# octopus_sch.net
KiCad netlist of a schematic drawn in Altium Designer
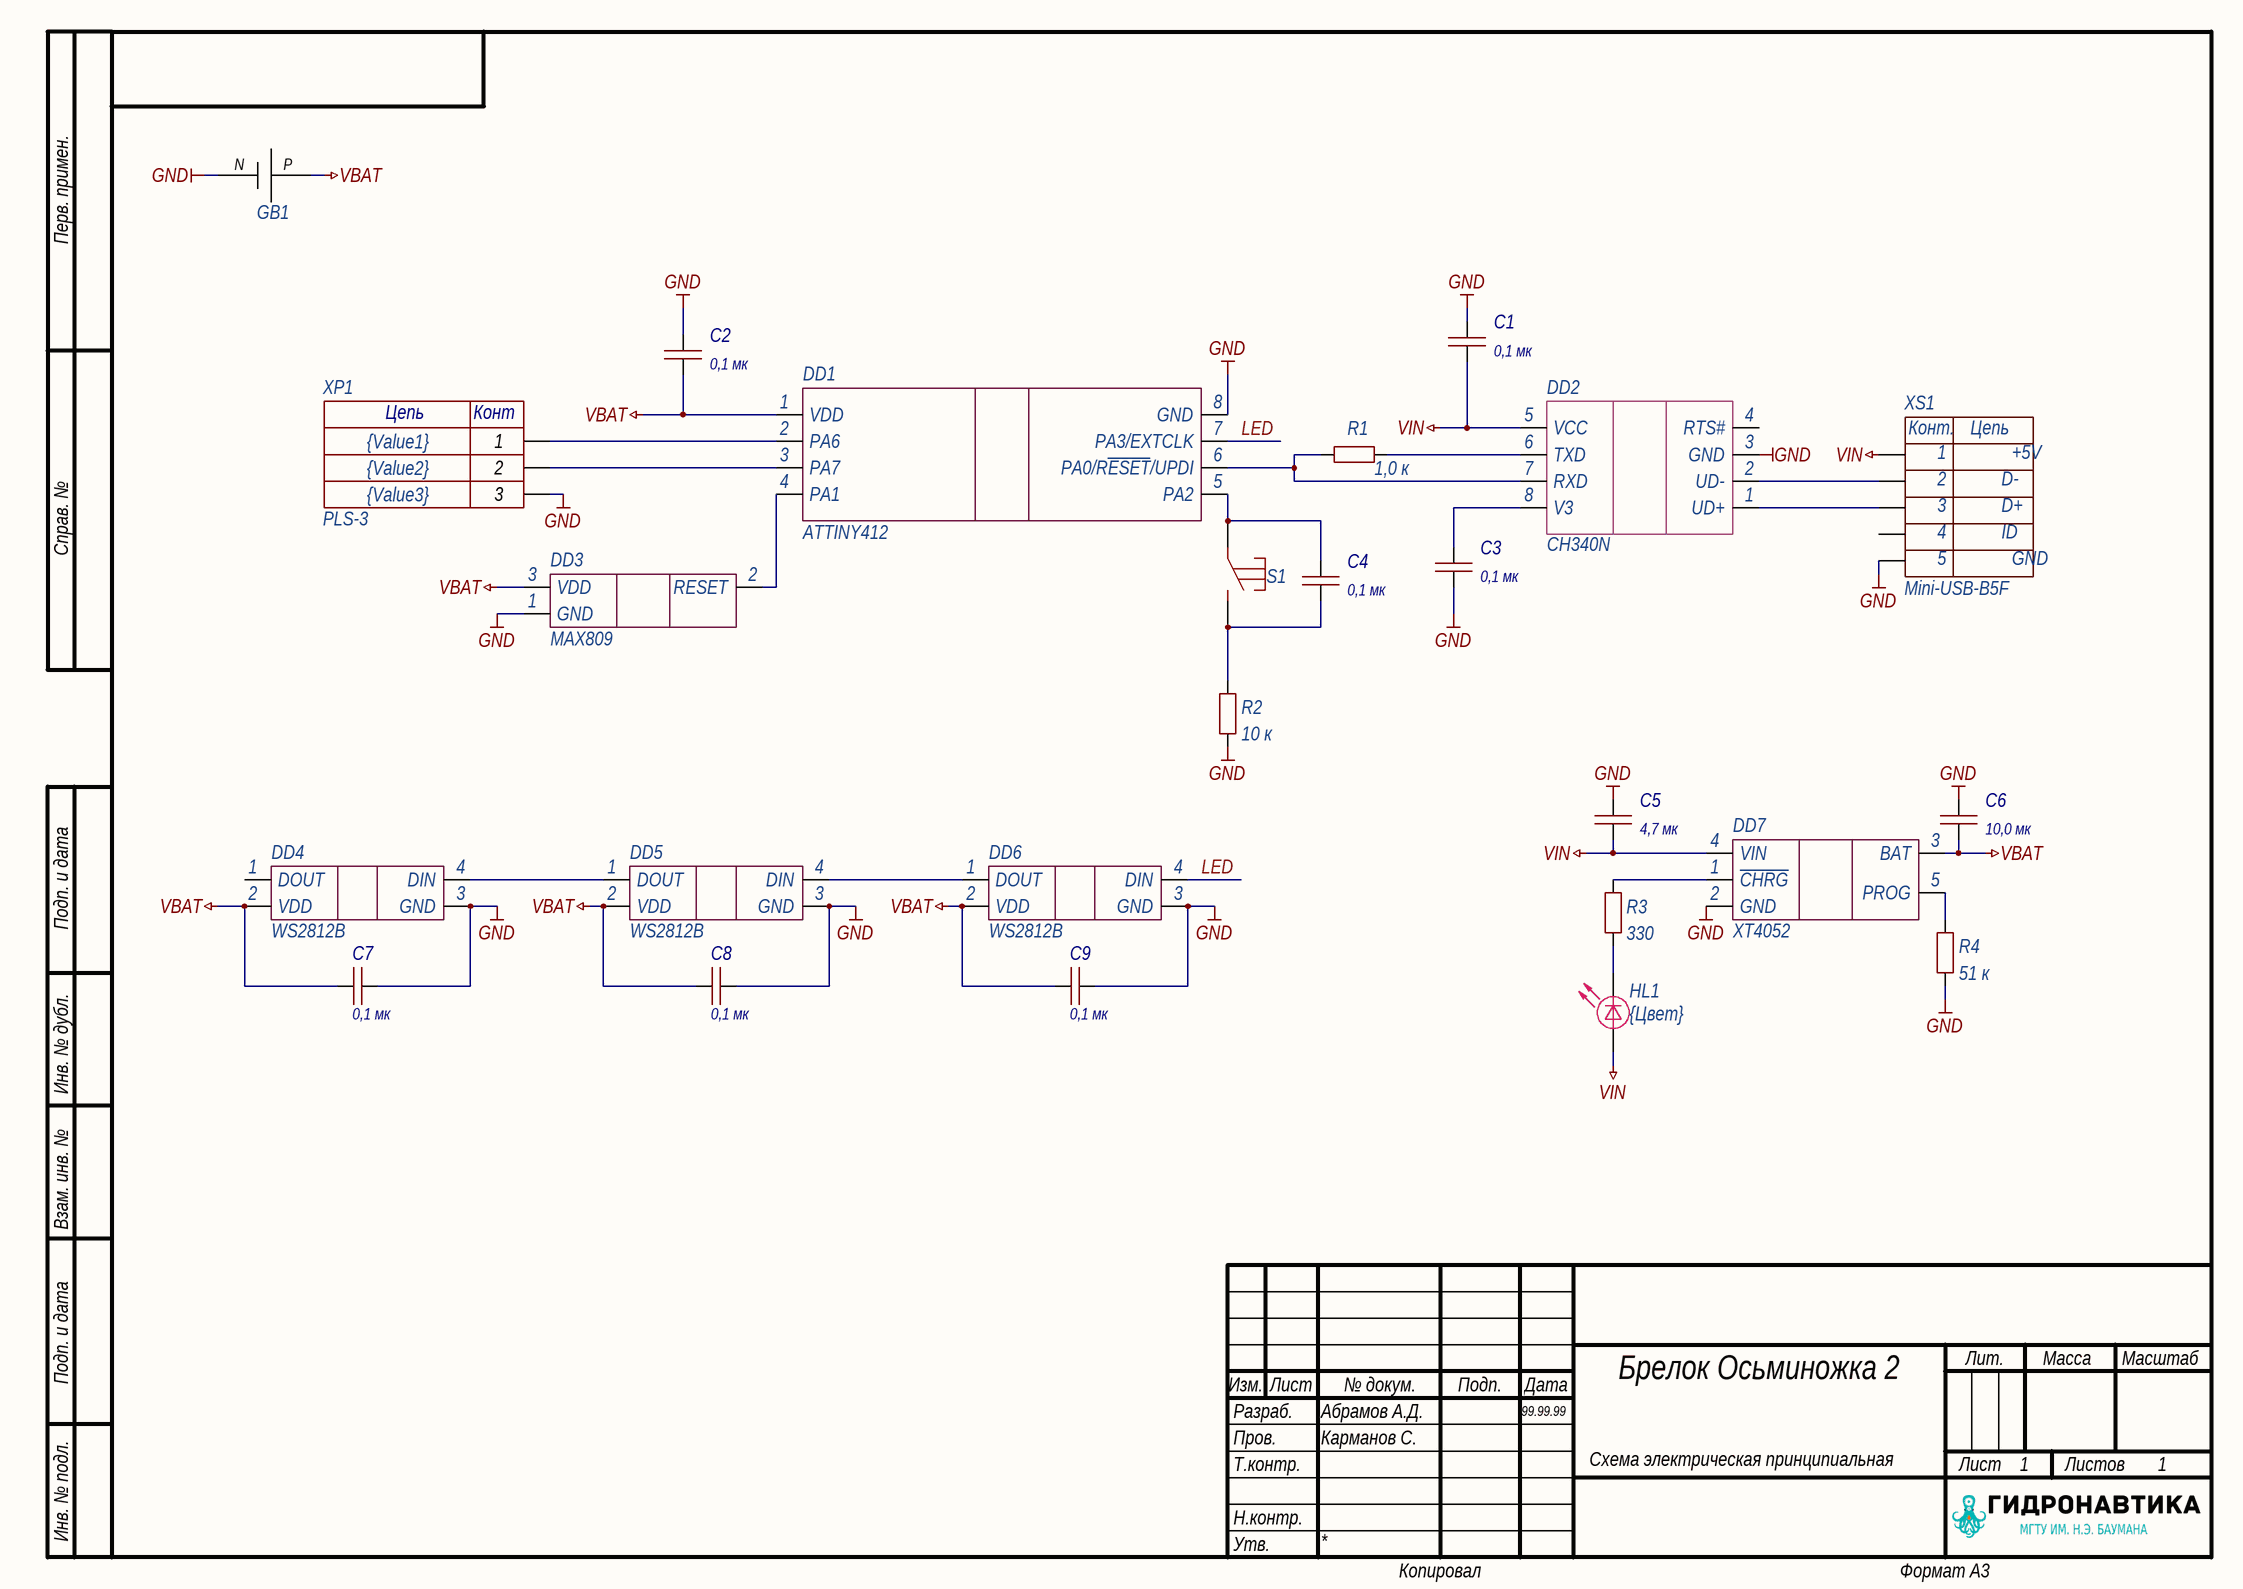
[diagram p0: octopus_sch.SchDoc]

(export (version "E")
  (design (tool "Eeschema 10.0.6"))
  (components
    (comp (ref "C1")
      (value "0,1 мк")
      (footprint "THT_0805")
      (description "Конденсатор")
      (fields (field (name "PART NUMBER") "Capacitor"))
      (libsource (lib "Hydrolib") (part "Capacitor"))
    )
    (comp (ref "C2")
      (value "0,1 мк")
      (footprint "THT_0805")
      (description "Конденсатор")
      (fields (field (name "PART NUMBER") "Capacitor"))
      (libsource (lib "Hydrolib") (part "Capacitor"))
    )
    (comp (ref "C3")
      (value "0,1 мк")
      (footprint "THT_0805")
      (description "Конденсатор")
      (fields (field (name "PART NUMBER") "Capacitor"))
      (libsource (lib "Hydrolib") (part "Capacitor"))
    )
    (comp (ref "C4")
      (value "0,1 мк")
      (footprint "THT_0805")
      (description "Конденсатор")
      (fields (field (name "PART NUMBER") "Capacitor"))
      (libsource (lib "Hydrolib") (part "Capacitor"))
    )
    (comp (ref "C5")
      (value "4,7 мк")
      (footprint "THT_0805")
      (description "Конденсатор")
      (fields (field (name "PART NUMBER") "Capacitor"))
      (libsource (lib "Hydrolib") (part "Capacitor"))
    )
    (comp (ref "C6")
      (value "10,0 мк")
      (footprint "THT_0805")
      (description "Конденсатор")
      (fields (field (name "PART NUMBER") "Capacitor"))
      (libsource (lib "Hydrolib") (part "Capacitor"))
    )
    (comp (ref "C7")
      (value "0,1 мк")
      (footprint "THT_0805")
      (description "Конденсатор")
      (fields (field (name "PART NUMBER") "Capacitor"))
      (libsource (lib "Hydrolib") (part "Capacitor"))
    )
    (comp (ref "C8")
      (value "0,1 мк")
      (footprint "THT_0805")
      (description "Конденсатор")
      (fields (field (name "PART NUMBER") "Capacitor"))
      (libsource (lib "Hydrolib") (part "Capacitor"))
    )
    (comp (ref "C9")
      (value "0,1 мк")
      (footprint "THT_0805")
      (description "Конденсатор")
      (fields (field (name "PART NUMBER") "Capacitor"))
      (libsource (lib "Hydrolib") (part "Capacitor"))
    )
    (comp (ref "DD1")
      (value "ATTINY412")
      (footprint "SOIC-8")
      (description "Микроконтроллер")
      (fields (field (name "АВТОР") "klegot"))
      (libsource (lib "Hydrolib") (part "ATTINY412"))
    )
    (comp (ref "DD2")
      (value "CH340N")
      (footprint "SOP8")
      (description "Преобразователь интерфейса USB в UART")
      (fields (field (name "АВТОР") "klegot"))
      (libsource (lib "Hydrolib") (part "CH340N"))
    )
    (comp (ref "DD3")
      (value "MAX809")
      (footprint "SOT23-3")
      (description "Формирователь импульса сброса (супервизор питания)")
      (fields (field (name "АВТОР") "klegot"))
      (libsource (lib "Hydrolib") (part "MAX809"))
    )
    (comp (ref "DD4")
      (value "WS2812B")
      (footprint "LED RGB horizontal")
      (description "Адресный светодиод")
      (fields (field (name "АВТОР") "klegot"))
      (libsource (lib "Hydrolib") (part "WS2812B"))
    )
    (comp (ref "DD5")
      (value "WS2812B")
      (footprint "LED_RGB_5MM")
      (description "Адресный светодиод")
      (fields (field (name "АВТОР") "klegot"))
      (libsource (lib "Hydrolib") (part "WS2812B"))
    )
    (comp (ref "DD6")
      (value "WS2812B")
      (footprint "LED_RGB_5MM")
      (description "Адресный светодиод")
      (fields (field (name "АВТОР") "klegot"))
      (libsource (lib "Hydrolib") (part "WS2812B"))
    )
    (comp (ref "DD7")
      (value "XT4052")
      (footprint "SOT23-5")
      (description "Контроллер заряда Li-Ion аккумуляторов, 4.2 В")
      (fields (field (name "АВТОР") "klegot"))
      (libsource (lib "Hydrolib") (part "XT4052"))
    )
    (comp (ref "GB1")
      (value "L-KLS5-CR2032-03")
      (footprint "L-KLS5-CR2032-03")
      (description "Держатель батареи CR2032")
      (fields (field (name "АВТОР") "klegot"))
      (libsource (lib "Hydrolib") (part "Battery"))
    )
    (comp (ref "HL1")
      (value "LED")
      (footprint "3mm_led_red")
      (description "Светодиод")
      (fields (field (name "COLOR") "{Цвет}"))
      (libsource (lib "Hydrolib") (part "LED"))
    )
    (comp (ref "R1")
      (value "1,0 к")
      (footprint "RES_THT_025W_1k")
      (description "Резистор номиналом 1,0 кОм 1%")
      (fields (field (name "PART NUMBER") "Resistor_1.0k_1_0603") (field (name "TOLERANCE") "1%"))
      (libsource (lib "") (part "Resistor_1"))
    )
    (comp (ref "R2")
      (value "10 к")
      (footprint "RES_THT_025W_10k")
      (description "Резистор номиналом 10 кОм 1%")
      (fields (field (name "PART NUMBER") "Resistor_10k_1_0603") (field (name "TOLERANCE") "1%"))
      (libsource (lib "") (part "Resistor_2"))
    )
    (comp (ref "R3")
      (value "330")
      (footprint "RES_THT_025W_1k")
      (description "Резистор номиналом 1,0 кОм 1%")
      (fields (field (name "PART NUMBER") "Resistor_1.0k_1_0603") (field (name "TOLERANCE") "1%"))
      (libsource (lib "Hydrolib") (part "Resistor"))
    )
    (comp (ref "R4")
      (value "51 к")
      (footprint "RES_THT_025W_100k")
      (description "Резистор номиналом 100 кОм 1%")
      (fields (field (name "PART NUMBER") "Resistor_100k_1_0603") (field (name "TOLERANCE") "1%"))
      (libsource (lib "Hydrolib") (part "Resistor"))
    )
    (comp (ref "S1")
      (value "KLS7-TS3601")
      (footprint "KLS7-TS3601")
      (description "Тактовая кнопка")
      (fields (field (name "АВТОР") "klegot"))
      (libsource (lib "Hydrolib") (part "Tact_button"))
    )
    (comp (ref "XP1")
      (value "PLS-3")
      (footprint "PLS3")
      (description "Гребенка 3 пина")
      (fields
        (field (name "VALUE3") "{Value3}")
        (field (name "VALUE2") "{Value2}")
        (field (name "VALUE1") "{Value1}")
        (field (name "АВТОР") "rreali")
      )
      (libsource (lib "Hydrolib") (part "Conn_3pin"))
    )
    (comp (ref "XS1")
      (value "Mini-USB-B5F")
      (footprint "KLS1-229-5FA")
      (description "Разъем mini USB, розетка угловая на плату")
      (fields (field (name "АВТОР") "klegot"))
      (libsource (lib "Hydrolib") (part "Mini-USB-B5F"))
    )
  )
  (nets
    (net (code "1") (name "/LED") (class "Default")
      (node (ref "DD1") (pin "7") (pinfunction "PA3/EXTCLK_7") (pintype "passive"))
      (node (ref "DD6") (pin "4") (pinfunction "DIN_4") (pintype "passive"))
    )
    (net (code "2") (name "GND") (class "Default")
      (node (ref "C1") (pin "2") (pinfunction "2_2") (pintype "passive"))
      (node (ref "C2") (pin "2") (pinfunction "2_2") (pintype "passive"))
      (node (ref "C3") (pin "1") (pinfunction "1_1") (pintype "passive"))
      (node (ref "C5") (pin "2") (pinfunction "2_2") (pintype "passive"))
      (node (ref "C6") (pin "2") (pinfunction "2_2") (pintype "passive"))
      (node (ref "C7") (pin "1") (pinfunction "1_1") (pintype "passive"))
      (node (ref "C8") (pin "1") (pinfunction "1_1") (pintype "passive"))
      (node (ref "C9") (pin "1") (pinfunction "1_1") (pintype "passive"))
      (node (ref "DD1") (pin "8") (pinfunction "GND_8") (pintype "passive"))
      (node (ref "DD2") (pin "3") (pinfunction "GND_3") (pintype "passive"))
      (node (ref "DD3") (pin "1") (pinfunction "GND_1") (pintype "passive"))
      (node (ref "DD4") (pin "3") (pinfunction "GND_3") (pintype "passive"))
      (node (ref "DD5") (pin "3") (pinfunction "GND_3") (pintype "passive"))
      (node (ref "DD6") (pin "3") (pinfunction "GND_3") (pintype "passive"))
      (node (ref "DD7") (pin "2") (pinfunction "GND_2") (pintype "passive"))
      (node (ref "GB1") (pin "N") (pinfunction "N_N") (pintype "passive"))
      (node (ref "R2") (pin "2") (pinfunction "2_2") (pintype "passive"))
      (node (ref "R4") (pin "1") (pinfunction "1_1") (pintype "passive"))
      (node (ref "XP1") (pin "3") (pinfunction "3_3") (pintype "passive"))
      (node (ref "XS1") (pin "5") (pinfunction "5_5") (pintype "passive"))
    )
    (net (code "3") (name "Net-(C4-Pad1)") (class "Default")
      (node (ref "C4") (pin "1") (pinfunction "1_1") (pintype "passive"))
      (node (ref "R2") (pin "1") (pinfunction "1_1") (pintype "passive"))
      (node (ref "S1") (pin "2") (pinfunction "2_2") (pintype "passive"))
    )
    (net (code "4") (name "Net-(DD1-PA0{slash}R~{ESET}{slash}UPDI)") (class "Default")
      (node (ref "DD1") (pin "6") (pinfunction "PA0/R~{ESET}/UPDI_6") (pintype "passive"))
      (node (ref "DD2") (pin "7") (pinfunction "RXD_7") (pintype "passive"))
      (node (ref "R1") (pin "1") (pinfunction "1_1") (pintype "passive"))
    )
    (net (code "5") (name "Net-(DD1-PA1)") (class "Default")
      (node (ref "DD1") (pin "4") (pinfunction "PA1_4") (pintype "passive"))
      (node (ref "DD3") (pin "2") (pinfunction "RESET_2") (pintype "passive"))
    )
    (net (code "6") (name "Net-(DD1-PA2)") (class "Default")
      (node (ref "C4") (pin "2") (pinfunction "2_2") (pintype "passive"))
      (node (ref "DD1") (pin "5") (pinfunction "PA2_5") (pintype "passive"))
      (node (ref "S1") (pin "1") (pinfunction "1_1") (pintype "passive"))
    )
    (net (code "7") (name "Net-(DD1-PA6)") (class "Default")
      (node (ref "DD1") (pin "2") (pinfunction "PA6_2") (pintype "passive"))
      (node (ref "XP1") (pin "1") (pinfunction "1_1") (pintype "passive"))
    )
    (net (code "8") (name "Net-(DD1-PA7)") (class "Default")
      (node (ref "DD1") (pin "3") (pinfunction "PA7_3") (pintype "passive"))
      (node (ref "XP1") (pin "2") (pinfunction "2_2") (pintype "passive"))
    )
    (net (code "9") (name "Net-(DD2-TXD)") (class "Default")
      (node (ref "DD2") (pin "6") (pinfunction "TXD_6") (pintype "passive"))
      (node (ref "R1") (pin "2") (pinfunction "2_2") (pintype "passive"))
    )
    (net (code "10") (name "Net-(DD2-UD+)") (class "Default")
      (node (ref "DD2") (pin "1") (pinfunction "UD+_1") (pintype "passive"))
      (node (ref "XS1") (pin "3") (pinfunction "3_3") (pintype "passive"))
    )
    (net (code "11") (name "Net-(DD2-UD-)") (class "Default")
      (node (ref "DD2") (pin "2") (pinfunction "UD-_2") (pintype "passive"))
      (node (ref "XS1") (pin "2") (pinfunction "2_2") (pintype "passive"))
    )
    (net (code "12") (name "Net-(DD2-V3)") (class "Default")
      (node (ref "C3") (pin "2") (pinfunction "2_2") (pintype "passive"))
      (node (ref "DD2") (pin "8") (pinfunction "V3_8") (pintype "passive"))
    )
    (net (code "13") (name "Net-(DD4-DIN)") (class "Default")
      (node (ref "DD4") (pin "4") (pinfunction "DIN_4") (pintype "passive"))
      (node (ref "DD5") (pin "1") (pinfunction "DOUT_1") (pintype "passive"))
    )
    (net (code "14") (name "Net-(DD5-DIN)") (class "Default")
      (node (ref "DD5") (pin "4") (pinfunction "DIN_4") (pintype "passive"))
      (node (ref "DD6") (pin "1") (pinfunction "DOUT_1") (pintype "passive"))
    )
    (net (code "15") (name "Net-(DD7-PROG)") (class "Default")
      (node (ref "DD7") (pin "5") (pinfunction "PROG_5") (pintype "passive"))
      (node (ref "R4") (pin "2") (pinfunction "2_2") (pintype "passive"))
    )
    (net (code "16") (name "Net-(DD7-~{CHRG})") (class "Default")
      (node (ref "DD7") (pin "1") (pinfunction "~{CHRG}_1") (pintype "passive"))
      (node (ref "R3") (pin "2") (pinfunction "2_2") (pintype "passive"))
    )
    (net (code "17") (name "Net-(HL1-Pad2)") (class "Default")
      (node (ref "HL1") (pin "2") (pinfunction "2_2") (pintype "passive"))
      (node (ref "R3") (pin "1") (pinfunction "1_1") (pintype "passive"))
    )
    (net (code "18") (name "VBAT") (class "Default")
      (node (ref "C2") (pin "1") (pinfunction "1_1") (pintype "passive"))
      (node (ref "C6") (pin "1") (pinfunction "1_1") (pintype "passive"))
      (node (ref "C7") (pin "2") (pinfunction "2_2") (pintype "passive"))
      (node (ref "C8") (pin "2") (pinfunction "2_2") (pintype "passive"))
      (node (ref "C9") (pin "2") (pinfunction "2_2") (pintype "passive"))
      (node (ref "DD1") (pin "1") (pinfunction "VDD_1") (pintype "passive"))
      (node (ref "DD3") (pin "3") (pinfunction "VDD_3") (pintype "passive"))
      (node (ref "DD4") (pin "2") (pinfunction "VDD_2") (pintype "passive"))
      (node (ref "DD5") (pin "2") (pinfunction "VDD_2") (pintype "passive"))
      (node (ref "DD6") (pin "2") (pinfunction "VDD_2") (pintype "passive"))
      (node (ref "DD7") (pin "3") (pinfunction "BAT_3") (pintype "passive"))
      (node (ref "GB1") (pin "P") (pinfunction "P_P") (pintype "passive"))
    )
    (net (code "19") (name "VIN") (class "Default")
      (node (ref "C1") (pin "1") (pinfunction "1_1") (pintype "passive"))
      (node (ref "C5") (pin "1") (pinfunction "1_1") (pintype "passive"))
      (node (ref "DD2") (pin "5") (pinfunction "VCC_5") (pintype "passive"))
      (node (ref "DD7") (pin "4") (pinfunction "VIN_4") (pintype "passive"))
      (node (ref "HL1") (pin "1") (pinfunction "1_1") (pintype "passive"))
      (node (ref "XS1") (pin "1") (pinfunction "1_1") (pintype "passive"))
    )
    (net (code "20") (name "unconnected-(DD2-RTS#-Pad4)") (class "Default")
      (node (ref "DD2") (pin "4") (pinfunction "RTS#_4") (pintype "passive"))
    )
    (net (code "21") (name "unconnected-(DD4-DOUT-Pad1)") (class "Default")
      (node (ref "DD4") (pin "1") (pinfunction "DOUT_1") (pintype "passive"))
    )
    (net (code "22") (name "unconnected-(XS1-Pad4)") (class "Default")
      (node (ref "XS1") (pin "4") (pinfunction "4_4") (pintype "passive"))
    )
  )
)
